# chaves.net
KiCad netlist of a schematic drawn in EAGLE
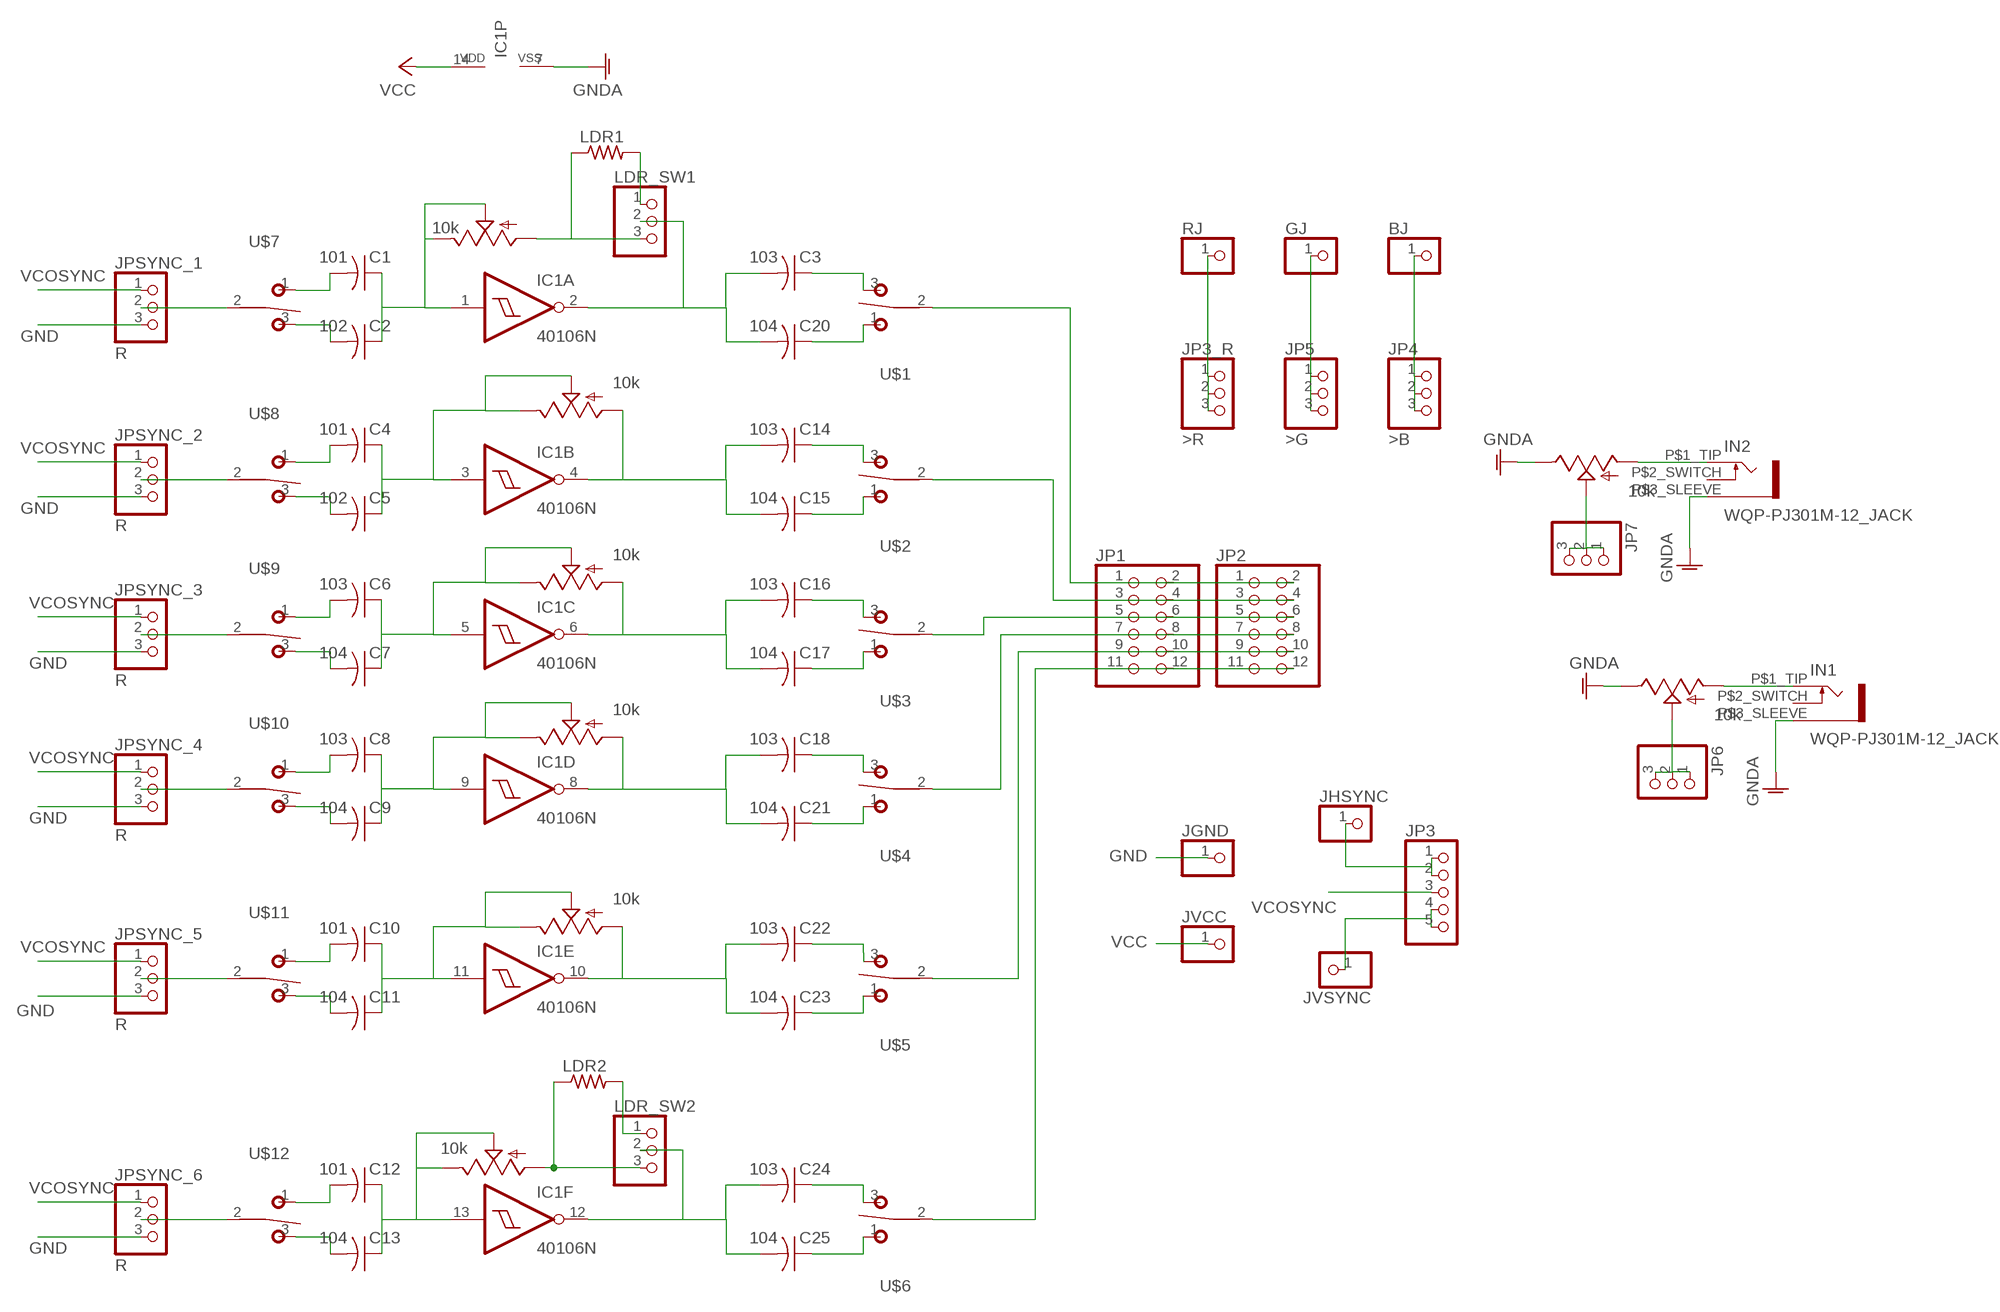
[diagram p0: schematic, sheet 1]

(export (version "E")
  (design (tool "Eeschema 10.0.6"))
  (components
    (comp (ref "BJ")
      (value "PINHD-1X1")
      (footprint "eagle-import:1X01")
      (libsource (lib "eagle-import") (part "PINHD-1X1"))
    )
    (comp (ref "C1")
      (value "101")
      (footprint "eagle-import:C050-025X075")
      (libsource (lib "eagle-import") (part "C-US050-025X075"))
    )
    (comp (ref "C2")
      (value "102")
      (footprint "eagle-import:C050-025X075")
      (libsource (lib "eagle-import") (part "C-US050-025X075"))
    )
    (comp (ref "C3")
      (value "103")
      (footprint "eagle-import:C050-025X075")
      (libsource (lib "eagle-import") (part "C-US050-025X075"))
    )
    (comp (ref "C4")
      (value "101")
      (footprint "eagle-import:C050-025X075")
      (libsource (lib "eagle-import") (part "C-US050-025X075"))
    )
    (comp (ref "C5")
      (value "102")
      (footprint "eagle-import:C050-025X075")
      (libsource (lib "eagle-import") (part "C-US050-025X075"))
    )
    (comp (ref "C6")
      (value "103")
      (footprint "eagle-import:C050-025X075")
      (libsource (lib "eagle-import") (part "C-US050-025X075"))
    )
    (comp (ref "C7")
      (value "104")
      (footprint "eagle-import:C050-025X075")
      (libsource (lib "eagle-import") (part "C-US050-025X075"))
    )
    (comp (ref "C8")
      (value "103")
      (footprint "eagle-import:C050-025X075")
      (libsource (lib "eagle-import") (part "C-US050-025X075"))
    )
    (comp (ref "C9")
      (value "104")
      (footprint "eagle-import:C050-025X075")
      (libsource (lib "eagle-import") (part "C-US050-025X075"))
    )
    (comp (ref "C10")
      (value "101")
      (footprint "eagle-import:C050-025X075")
      (libsource (lib "eagle-import") (part "C-US050-025X075"))
    )
    (comp (ref "C11")
      (value "104")
      (footprint "eagle-import:C050-025X075")
      (libsource (lib "eagle-import") (part "C-US050-025X075"))
    )
    (comp (ref "C12")
      (value "101")
      (footprint "eagle-import:C050-025X075")
      (libsource (lib "eagle-import") (part "C-US050-025X075"))
    )
    (comp (ref "C13")
      (value "104")
      (footprint "eagle-import:C050-025X075")
      (libsource (lib "eagle-import") (part "C-US050-025X075"))
    )
    (comp (ref "C14")
      (value "103")
      (footprint "eagle-import:C050-025X075")
      (libsource (lib "eagle-import") (part "C-US050-025X075"))
    )
    (comp (ref "C15")
      (value "104")
      (footprint "eagle-import:C050-025X075")
      (libsource (lib "eagle-import") (part "C-US050-025X075"))
    )
    (comp (ref "C16")
      (value "103")
      (footprint "eagle-import:C050-025X075")
      (libsource (lib "eagle-import") (part "C-US050-025X075"))
    )
    (comp (ref "C17")
      (value "104")
      (footprint "eagle-import:C050-025X075")
      (libsource (lib "eagle-import") (part "C-US050-025X075"))
    )
    (comp (ref "C18")
      (value "103")
      (footprint "eagle-import:C050-025X075")
      (libsource (lib "eagle-import") (part "C-US050-025X075"))
    )
    (comp (ref "C20")
      (value "104")
      (footprint "eagle-import:C050-025X075")
      (libsource (lib "eagle-import") (part "C-US050-025X075"))
    )
    (comp (ref "C21")
      (value "104")
      (footprint "eagle-import:C050-025X075")
      (libsource (lib "eagle-import") (part "C-US050-025X075"))
    )
    (comp (ref "C22")
      (value "103")
      (footprint "eagle-import:C050-025X075")
      (libsource (lib "eagle-import") (part "C-US050-025X075"))
    )
    (comp (ref "C23")
      (value "104")
      (footprint "eagle-import:C050-025X075")
      (libsource (lib "eagle-import") (part "C-US050-025X075"))
    )
    (comp (ref "C24")
      (value "103")
      (footprint "eagle-import:C050-025X075")
      (libsource (lib "eagle-import") (part "C-US050-025X075"))
    )
    (comp (ref "C25")
      (value "104")
      (footprint "eagle-import:C050-025X075")
      (libsource (lib "eagle-import") (part "C-US050-025X075"))
    )
    (comp (ref "GJ")
      (value "PINHD-1X1")
      (footprint "eagle-import:1X01")
      (libsource (lib "eagle-import") (part "PINHD-1X1"))
    )
    (comp (ref "IC1")
      (value "40106N")
      (footprint "eagle-import:DIL14")
      (libsource (lib "eagle-import") (part "40106N"))
    )
    (comp (ref "IN1")
      (value "WQP-PJ301M-12_JACK")
      (footprint "eagle-import:WQP-PJ301M-12_JACK")
      (libsource (lib "eagle-import") (part "WQP-PJ301M-12_JACK"))
    )
    (comp (ref "IN2")
      (value "WQP-PJ301M-12_JACK")
      (footprint "eagle-import:WQP-PJ301M-12_JACK")
      (libsource (lib "eagle-import") (part "WQP-PJ301M-12_JACK"))
    )
    (comp (ref "JGND")
      (value "PINHD-1X1")
      (footprint "eagle-import:1X01")
      (libsource (lib "eagle-import") (part "PINHD-1X1"))
    )
    (comp (ref "JHSYNC")
      (value "PINHD-1X1")
      (footprint "eagle-import:1X01")
      (libsource (lib "eagle-import") (part "PINHD-1X1"))
    )
    (comp (ref "JP1")
      (value "PINHD-2X6")
      (footprint "eagle-import:2X06")
      (libsource (lib "eagle-import") (part "PINHD-2X6"))
    )
    (comp (ref "JP2")
      (value "PINHD-2X6")
      (footprint "eagle-import:2X06")
      (libsource (lib "eagle-import") (part "PINHD-2X6"))
    )
    (comp (ref "JP3")
      (value "PINHD-1X5")
      (footprint "eagle-import:1X05")
      (libsource (lib "eagle-import") (part "PINHD-1X5"))
    )
    (comp (ref "JP3_R")
      (value ">R")
      (footprint "eagle-import:1X03")
      (libsource (lib "eagle-import") (part "pinhead_PINHD-1X3"))
    )
    (comp (ref "JP4")
      (value ">B")
      (footprint "eagle-import:1X03")
      (libsource (lib "eagle-import") (part "pinhead_PINHD-1X3"))
    )
    (comp (ref "JP5")
      (value ">G")
      (footprint "eagle-import:1X03")
      (libsource (lib "eagle-import") (part "pinhead_PINHD-1X3"))
    )
    (comp (ref "JP6")
      (value "PINHD-1X3CB")
      (footprint "eagle-import:1X03-CLEANBIG")
      (libsource (lib "eagle-import") (part "PINHD-1X3CB"))
    )
    (comp (ref "JP7")
      (value "PINHD-1X3CB")
      (footprint "eagle-import:1X03-CLEANBIG")
      (libsource (lib "eagle-import") (part "PINHD-1X3CB"))
    )
    (comp (ref "JPSYNC_1")
      (value "R")
      (footprint "eagle-import:1X03")
      (libsource (lib "eagle-import") (part "pinhead_PINHD-1X3"))
    )
    (comp (ref "JPSYNC_2")
      (value "R")
      (footprint "eagle-import:1X03")
      (libsource (lib "eagle-import") (part "pinhead_PINHD-1X3"))
    )
    (comp (ref "JPSYNC_3")
      (value "R")
      (footprint "eagle-import:1X03")
      (libsource (lib "eagle-import") (part "pinhead_PINHD-1X3"))
    )
    (comp (ref "JPSYNC_4")
      (value "R")
      (footprint "eagle-import:1X03")
      (libsource (lib "eagle-import") (part "pinhead_PINHD-1X3"))
    )
    (comp (ref "JPSYNC_5")
      (value "R")
      (footprint "eagle-import:1X03")
      (libsource (lib "eagle-import") (part "pinhead_PINHD-1X3"))
    )
    (comp (ref "JPSYNC_6")
      (value "R")
      (footprint "eagle-import:1X03")
      (libsource (lib "eagle-import") (part "pinhead_PINHD-1X3"))
    )
    (comp (ref "JVCC")
      (value "PINHD-1X1")
      (footprint "eagle-import:1X01")
      (libsource (lib "eagle-import") (part "PINHD-1X1"))
    )
    (comp (ref "JVSYNC")
      (value "PINHD-1X1")
      (footprint "eagle-import:1X01")
      (libsource (lib "eagle-import") (part "PINHD-1X1"))
    )
    (comp (ref "LDR1")
      (value "R-US_0204/7")
      (footprint "eagle-import:0204_7")
      (libsource (lib "eagle-import") (part "R-US_0204/7"))
    )
    (comp (ref "LDR2")
      (value "R-US_0204/7")
      (footprint "eagle-import:0204_7")
      (libsource (lib "eagle-import") (part "R-US_0204/7"))
    )
    (comp (ref "LDR_SW1")
      (value "PINHD-1X3")
      (footprint "eagle-import:1X03")
      (libsource (lib "eagle-import") (part "pinhead_PINHD-1X3"))
    )
    (comp (ref "LDR_SW2")
      (value "PINHD-1X3")
      (footprint "eagle-import:1X03")
      (libsource (lib "eagle-import") (part "pinhead_PINHD-1X3"))
    )
    (comp (ref "POT1")
      (value "10k")
      (footprint "eagle-import:ALPS_POT_VERTICAL")
      (libsource (lib "eagle-import") (part "POT_USVERTICAL"))
    )
    (comp (ref "POT2")
      (value "10k")
      (footprint "eagle-import:ALPS_POT_VERTICAL")
      (libsource (lib "eagle-import") (part "POT_USVERTICAL"))
    )
    (comp (ref "POT3")
      (value "10k")
      (footprint "eagle-import:ALPS_POT_VERTICAL")
      (libsource (lib "eagle-import") (part "POT_USVERTICAL"))
    )
    (comp (ref "POT4")
      (value "10k")
      (footprint "eagle-import:ALPS_POT_VERTICAL")
      (libsource (lib "eagle-import") (part "POT_USVERTICAL"))
    )
    (comp (ref "POT5")
      (value "10k")
      (footprint "eagle-import:ALPS_POT_VERTICAL")
      (libsource (lib "eagle-import") (part "POT_USVERTICAL"))
    )
    (comp (ref "POT6")
      (value "10k")
      (footprint "eagle-import:ALPS_POT_VERTICAL")
      (libsource (lib "eagle-import") (part "POT_USVERTICAL"))
    )
    (comp (ref "POT7")
      (value "10k")
      (footprint "eagle-import:ALPS_POT_VERTICAL")
      (libsource (lib "eagle-import") (part "POT_USVERTICAL"))
    )
    (comp (ref "POT8")
      (value "10k")
      (footprint "eagle-import:ALPS_POT_VERTICAL")
      (libsource (lib "eagle-import") (part "POT_USVERTICAL"))
    )
    (comp (ref "RJ")
      (value "PINHD-1X1")
      (footprint "eagle-import:1X01")
      (libsource (lib "eagle-import") (part "PINHD-1X1"))
    )
    (comp (ref "U$1")
      (value "T-80-T-SPDT-ON-OFF-ON")
      (footprint "eagle-import:M9040P")
      (libsource (lib "eagle-import") (part "T-80-T-SPDT-ON-OFF-ON"))
    )
    (comp (ref "U$2")
      (value "T-80-T-SPDT-ON-OFF-ON")
      (footprint "eagle-import:M9040P")
      (libsource (lib "eagle-import") (part "T-80-T-SPDT-ON-OFF-ON"))
    )
    (comp (ref "U$3")
      (value "T-80-T-SPDT-ON-OFF-ON")
      (footprint "eagle-import:M9040P")
      (libsource (lib "eagle-import") (part "T-80-T-SPDT-ON-OFF-ON"))
    )
    (comp (ref "U$4")
      (value "T-80-T-SPDT-ON-OFF-ON")
      (footprint "eagle-import:M9040P")
      (libsource (lib "eagle-import") (part "T-80-T-SPDT-ON-OFF-ON"))
    )
    (comp (ref "U$5")
      (value "T-80-T-SPDT-ON-OFF-ON")
      (footprint "eagle-import:M9040P")
      (libsource (lib "eagle-import") (part "T-80-T-SPDT-ON-OFF-ON"))
    )
    (comp (ref "U$6")
      (value "T-80-T-SPDT-ON-OFF-ON")
      (footprint "eagle-import:M9040P")
      (libsource (lib "eagle-import") (part "T-80-T-SPDT-ON-OFF-ON"))
    )
    (comp (ref "U$7")
      (value "T-80-T-SPDT-ON-OFF-ON")
      (footprint "eagle-import:M9040P")
      (libsource (lib "eagle-import") (part "T-80-T-SPDT-ON-OFF-ON"))
    )
    (comp (ref "U$8")
      (value "T-80-T-SPDT-ON-OFF-ON")
      (footprint "eagle-import:M9040P")
      (libsource (lib "eagle-import") (part "T-80-T-SPDT-ON-OFF-ON"))
    )
    (comp (ref "U$9")
      (value "T-80-T-SPDT-ON-OFF-ON")
      (footprint "eagle-import:M9040P")
      (libsource (lib "eagle-import") (part "T-80-T-SPDT-ON-OFF-ON"))
    )
    (comp (ref "U$10")
      (value "T-80-T-SPDT-ON-OFF-ON")
      (footprint "eagle-import:M9040P")
      (libsource (lib "eagle-import") (part "T-80-T-SPDT-ON-OFF-ON"))
    )
    (comp (ref "U$11")
      (value "T-80-T-SPDT-ON-OFF-ON")
      (footprint "eagle-import:M9040P")
      (libsource (lib "eagle-import") (part "T-80-T-SPDT-ON-OFF-ON"))
    )
    (comp (ref "U$12")
      (value "T-80-T-SPDT-ON-OFF-ON")
      (footprint "eagle-import:M9040P")
      (libsource (lib "eagle-import") (part "T-80-T-SPDT-ON-OFF-ON"))
    )
  )
  (nets
    (net (code "1") (name "/VCOSYNC") (class "Default")
      (node (ref "JP3") (pin "3") (pinfunction "3_3") (pintype "passive"))
      (node (ref "JPSYNC_1") (pin "1") (pinfunction "1_1") (pintype "passive"))
      (node (ref "JPSYNC_2") (pin "1") (pinfunction "1_1") (pintype "passive"))
      (node (ref "JPSYNC_3") (pin "1") (pinfunction "1_1") (pintype "passive"))
      (node (ref "JPSYNC_4") (pin "1") (pinfunction "1_1") (pintype "passive"))
      (node (ref "JPSYNC_5") (pin "1") (pinfunction "1_1") (pintype "passive"))
      (node (ref "JPSYNC_6") (pin "1") (pinfunction "1_1") (pintype "passive"))
    )
    (net (code "2") (name "GNDA") (class "Default")
      (node (ref "IC1") (pin "7") (pinfunction "VSS_7") (pintype "power_in"))
      (node (ref "IN1") (pin "P$3_SLEEVE") (pinfunction "1_P$3_SLEEVE") (pintype "passive"))
      (node (ref "IN2") (pin "P$3_SLEEVE") (pinfunction "1_P$3_SLEEVE") (pintype "passive"))
      (node (ref "JGND") (pin "1") (pinfunction "1_1") (pintype "passive"))
      (node (ref "JPSYNC_1") (pin "3") (pinfunction "3_3") (pintype "passive"))
      (node (ref "JPSYNC_2") (pin "3") (pinfunction "3_3") (pintype "passive"))
      (node (ref "JPSYNC_3") (pin "3") (pinfunction "3_3") (pintype "passive"))
      (node (ref "JPSYNC_4") (pin "3") (pinfunction "3_3") (pintype "passive"))
      (node (ref "JPSYNC_5") (pin "3") (pinfunction "3_3") (pintype "passive"))
      (node (ref "JPSYNC_6") (pin "3") (pinfunction "3_3") (pintype "passive"))
      (node (ref "POT7") (pin "P$1") (pinfunction "E_P$1") (pintype "passive"))
      (node (ref "POT8") (pin "P$1") (pinfunction "E_P$1") (pintype "passive"))
    )
    (net (code "3") (name "Net-(BJ-Pad1)") (class "Default")
      (node (ref "BJ") (pin "1") (pinfunction "1_1") (pintype "passive"))
      (node (ref "JP4") (pin "1") (pinfunction "1_1") (pintype "passive"))
      (node (ref "JP4") (pin "2") (pinfunction "2_2") (pintype "passive"))
      (node (ref "JP4") (pin "3") (pinfunction "3_3") (pintype "passive"))
    )
    (net (code "4") (name "Net-(GJ-Pad1)") (class "Default")
      (node (ref "GJ") (pin "1") (pinfunction "1_1") (pintype "passive"))
      (node (ref "JP5") (pin "1") (pinfunction "1_1") (pintype "passive"))
      (node (ref "JP5") (pin "2") (pinfunction "2_2") (pintype "passive"))
      (node (ref "JP5") (pin "3") (pinfunction "3_3") (pintype "passive"))
    )
    (net (code "5") (name "Net-(IC1A-I)") (class "Default")
      (node (ref "C1") (pin "1") (pinfunction "1_1") (pintype "passive"))
      (node (ref "C2") (pin "1") (pinfunction "1_1") (pintype "passive"))
      (node (ref "IC1") (pin "1") (pinfunction "I_1") (pintype "input"))
      (node (ref "POT1") (pin "P$1") (pinfunction "E_P$1") (pintype "passive"))
      (node (ref "POT1") (pin "P$2") (pinfunction "S_P$2") (pintype "passive"))
    )
    (net (code "6") (name "Net-(IC1A-O)") (class "Default")
      (node (ref "C20") (pin "2") (pinfunction "2_2") (pintype "passive"))
      (node (ref "C3") (pin "2") (pinfunction "2_2") (pintype "passive"))
      (node (ref "IC1") (pin "2") (pinfunction "O_2") (pintype "output"))
      (node (ref "LDR_SW1") (pin "2") (pinfunction "2_2") (pintype "passive"))
    )
    (net (code "7") (name "Net-(IC1B-I)") (class "Default")
      (node (ref "C4") (pin "1") (pinfunction "1_1") (pintype "passive"))
      (node (ref "C5") (pin "1") (pinfunction "1_1") (pintype "passive"))
      (node (ref "IC1") (pin "3") (pinfunction "I_3") (pintype "input"))
      (node (ref "POT2") (pin "P$1") (pinfunction "E_P$1") (pintype "passive"))
      (node (ref "POT2") (pin "P$2") (pinfunction "S_P$2") (pintype "passive"))
    )
    (net (code "8") (name "Net-(IC1B-O)") (class "Default")
      (node (ref "C14") (pin "2") (pinfunction "2_2") (pintype "passive"))
      (node (ref "C15") (pin "2") (pinfunction "2_2") (pintype "passive"))
      (node (ref "IC1") (pin "4") (pinfunction "O_4") (pintype "output"))
      (node (ref "POT2") (pin "P$3") (pinfunction "A_P$3") (pintype "passive"))
    )
    (net (code "9") (name "Net-(IC1C-I)") (class "Default")
      (node (ref "C6") (pin "1") (pinfunction "1_1") (pintype "passive"))
      (node (ref "C7") (pin "1") (pinfunction "1_1") (pintype "passive"))
      (node (ref "IC1") (pin "5") (pinfunction "I_5") (pintype "input"))
      (node (ref "POT3") (pin "P$1") (pinfunction "E_P$1") (pintype "passive"))
      (node (ref "POT3") (pin "P$2") (pinfunction "S_P$2") (pintype "passive"))
    )
    (net (code "10") (name "Net-(IC1C-O)") (class "Default")
      (node (ref "C16") (pin "2") (pinfunction "2_2") (pintype "passive"))
      (node (ref "C17") (pin "2") (pinfunction "2_2") (pintype "passive"))
      (node (ref "IC1") (pin "6") (pinfunction "O_6") (pintype "output"))
      (node (ref "POT3") (pin "P$3") (pinfunction "A_P$3") (pintype "passive"))
    )
    (net (code "11") (name "Net-(IC1D-I)") (class "Default")
      (node (ref "C8") (pin "1") (pinfunction "1_1") (pintype "passive"))
      (node (ref "C9") (pin "1") (pinfunction "1_1") (pintype "passive"))
      (node (ref "IC1") (pin "9") (pinfunction "I_9") (pintype "input"))
      (node (ref "POT4") (pin "P$1") (pinfunction "E_P$1") (pintype "passive"))
      (node (ref "POT4") (pin "P$2") (pinfunction "S_P$2") (pintype "passive"))
    )
    (net (code "12") (name "Net-(IC1D-O)") (class "Default")
      (node (ref "C18") (pin "2") (pinfunction "2_2") (pintype "passive"))
      (node (ref "C21") (pin "2") (pinfunction "2_2") (pintype "passive"))
      (node (ref "IC1") (pin "8") (pinfunction "O_8") (pintype "output"))
      (node (ref "POT4") (pin "P$3") (pinfunction "A_P$3") (pintype "passive"))
    )
    (net (code "13") (name "Net-(IC1E-I)") (class "Default")
      (node (ref "C10") (pin "1") (pinfunction "1_1") (pintype "passive"))
      (node (ref "C11") (pin "1") (pinfunction "1_1") (pintype "passive"))
      (node (ref "IC1") (pin "11") (pinfunction "I_11") (pintype "input"))
      (node (ref "POT5") (pin "P$1") (pinfunction "E_P$1") (pintype "passive"))
      (node (ref "POT5") (pin "P$2") (pinfunction "S_P$2") (pintype "passive"))
    )
    (net (code "14") (name "Net-(IC1E-O)") (class "Default")
      (node (ref "C22") (pin "2") (pinfunction "2_2") (pintype "passive"))
      (node (ref "C23") (pin "2") (pinfunction "2_2") (pintype "passive"))
      (node (ref "IC1") (pin "10") (pinfunction "O_10") (pintype "output"))
      (node (ref "POT5") (pin "P$3") (pinfunction "A_P$3") (pintype "passive"))
    )
    (net (code "15") (name "Net-(IC1F-I)") (class "Default")
      (node (ref "C12") (pin "1") (pinfunction "1_1") (pintype "passive"))
      (node (ref "C13") (pin "1") (pinfunction "1_1") (pintype "passive"))
      (node (ref "IC1") (pin "13") (pinfunction "I_13") (pintype "input"))
      (node (ref "POT6") (pin "P$1") (pinfunction "E_P$1") (pintype "passive"))
      (node (ref "POT6") (pin "P$2") (pinfunction "S_P$2") (pintype "passive"))
    )
    (net (code "16") (name "Net-(IC1F-O)") (class "Default")
      (node (ref "C24") (pin "2") (pinfunction "2_2") (pintype "passive"))
      (node (ref "C25") (pin "2") (pinfunction "2_2") (pintype "passive"))
      (node (ref "IC1") (pin "12") (pinfunction "O_12") (pintype "output"))
      (node (ref "LDR_SW2") (pin "2") (pinfunction "2_2") (pintype "passive"))
    )
    (net (code "17") (name "Net-(IN1-2)") (class "Default")
      (node (ref "IN1") (pin "P$1_TIP") (pinfunction "2_P$1_TIP") (pintype "passive"))
      (node (ref "POT7") (pin "P$3") (pinfunction "A_P$3") (pintype "passive"))
    )
    (net (code "18") (name "Net-(IN2-2)") (class "Default")
      (node (ref "IN2") (pin "P$1_TIP") (pinfunction "2_P$1_TIP") (pintype "passive"))
      (node (ref "POT8") (pin "P$3") (pinfunction "A_P$3") (pintype "passive"))
    )
    (net (code "19") (name "Net-(JHSYNC-Pad1)") (class "Default")
      (node (ref "JHSYNC") (pin "1") (pinfunction "1_1") (pintype "passive"))
      (node (ref "JP3") (pin "1") (pinfunction "1_1") (pintype "passive"))
      (node (ref "JP3") (pin "2") (pinfunction "2_2") (pintype "passive"))
    )
    (net (code "20") (name "Net-(JP3-Pad4)") (class "Default")
      (node (ref "JP3") (pin "4") (pinfunction "4_4") (pintype "passive"))
      (node (ref "JP3") (pin "5") (pinfunction "5_5") (pintype "passive"))
      (node (ref "JVSYNC") (pin "1") (pinfunction "1_1") (pintype "passive"))
    )
    (net (code "21") (name "Net-(JP3_R-Pad1)") (class "Default")
      (node (ref "JP3_R") (pin "1") (pinfunction "1_1") (pintype "passive"))
      (node (ref "JP3_R") (pin "2") (pinfunction "2_2") (pintype "passive"))
      (node (ref "JP3_R") (pin "3") (pinfunction "3_3") (pintype "passive"))
      (node (ref "RJ") (pin "1") (pinfunction "1_1") (pintype "passive"))
    )
    (net (code "22") (name "Net-(LDR1-Pad2)") (class "Default")
      (node (ref "LDR1") (pin "2") (pinfunction "2_2") (pintype "passive"))
      (node (ref "LDR_SW1") (pin "1") (pinfunction "1_1") (pintype "passive"))
    )
    (net (code "23") (name "Net-(LDR2-Pad2)") (class "Default")
      (node (ref "LDR2") (pin "2") (pinfunction "2_2") (pintype "passive"))
      (node (ref "LDR_SW2") (pin "1") (pinfunction "1_1") (pintype "passive"))
    )
    (net (code "24") (name "Net-(POT1-A)") (class "Default")
      (node (ref "LDR1") (pin "1") (pinfunction "1_1") (pintype "passive"))
      (node (ref "LDR_SW1") (pin "3") (pinfunction "3_3") (pintype "passive"))
      (node (ref "POT1") (pin "P$3") (pinfunction "A_P$3") (pintype "passive"))
    )
    (net (code "25") (name "Net-(POT6-A)") (class "Default")
      (node (ref "LDR2") (pin "1") (pinfunction "1_1") (pintype "passive"))
      (node (ref "LDR_SW2") (pin "3") (pinfunction "3_3") (pintype "passive"))
      (node (ref "POT6") (pin "P$3") (pinfunction "A_P$3") (pintype "passive"))
    )
    (net (code "26") (name "Net-(POT7-S)") (class "Default")
      (node (ref "JP6") (pin "1") (pinfunction "1_1") (pintype "passive"))
      (node (ref "JP6") (pin "2") (pinfunction "2_2") (pintype "passive"))
      (node (ref "JP6") (pin "3") (pinfunction "3_3") (pintype "passive"))
      (node (ref "POT7") (pin "P$2") (pinfunction "S_P$2") (pintype "passive"))
    )
    (net (code "27") (name "Net-(POT8-S)") (class "Default")
      (node (ref "JP7") (pin "1") (pinfunction "1_1") (pintype "passive"))
      (node (ref "JP7") (pin "2") (pinfunction "2_2") (pintype "passive"))
      (node (ref "JP7") (pin "3") (pinfunction "3_3") (pintype "passive"))
      (node (ref "POT8") (pin "P$2") (pinfunction "S_P$2") (pintype "passive"))
    )
    (net (code "28") (name "Net-(U$1-O)") (class "Default")
      (node (ref "C20") (pin "1") (pinfunction "1_1") (pintype "passive"))
      (node (ref "U$1") (pin "1") (pinfunction "O_1") (pintype "passive"))
    )
    (net (code "29") (name "Net-(U$1-P)") (class "Default")
      (node (ref "JP1") (pin "1") (pinfunction "1_1") (pintype "passive"))
      (node (ref "JP1") (pin "2") (pinfunction "2_2") (pintype "passive"))
      (node (ref "JP2") (pin "1") (pinfunction "1_1") (pintype "passive"))
      (node (ref "JP2") (pin "2") (pinfunction "2_2") (pintype "passive"))
      (node (ref "U$1") (pin "2") (pinfunction "P_2") (pintype "passive"))
    )
    (net (code "30") (name "Net-(U$1-S)") (class "Default")
      (node (ref "C3") (pin "1") (pinfunction "1_1") (pintype "passive"))
      (node (ref "U$1") (pin "3") (pinfunction "S_3") (pintype "passive"))
    )
    (net (code "31") (name "Net-(U$2-O)") (class "Default")
      (node (ref "C15") (pin "1") (pinfunction "1_1") (pintype "passive"))
      (node (ref "U$2") (pin "1") (pinfunction "O_1") (pintype "passive"))
    )
    (net (code "32") (name "Net-(U$2-P)") (class "Default")
      (node (ref "JP1") (pin "3") (pinfunction "3_3") (pintype "passive"))
      (node (ref "JP1") (pin "4") (pinfunction "4_4") (pintype "passive"))
      (node (ref "JP2") (pin "3") (pinfunction "3_3") (pintype "passive"))
      (node (ref "JP2") (pin "4") (pinfunction "4_4") (pintype "passive"))
      (node (ref "U$2") (pin "2") (pinfunction "P_2") (pintype "passive"))
    )
    (net (code "33") (name "Net-(U$2-S)") (class "Default")
      (node (ref "C14") (pin "1") (pinfunction "1_1") (pintype "passive"))
      (node (ref "U$2") (pin "3") (pinfunction "S_3") (pintype "passive"))
    )
    (net (code "34") (name "Net-(U$3-O)") (class "Default")
      (node (ref "C17") (pin "1") (pinfunction "1_1") (pintype "passive"))
      (node (ref "U$3") (pin "1") (pinfunction "O_1") (pintype "passive"))
    )
    (net (code "35") (name "Net-(U$3-P)") (class "Default")
      (node (ref "JP1") (pin "5") (pinfunction "5_5") (pintype "passive"))
      (node (ref "JP1") (pin "6") (pinfunction "6_6") (pintype "passive"))
      (node (ref "JP2") (pin "5") (pinfunction "5_5") (pintype "passive"))
      (node (ref "JP2") (pin "6") (pinfunction "6_6") (pintype "passive"))
      (node (ref "U$3") (pin "2") (pinfunction "P_2") (pintype "passive"))
    )
    (net (code "36") (name "Net-(U$3-S)") (class "Default")
      (node (ref "C16") (pin "1") (pinfunction "1_1") (pintype "passive"))
      (node (ref "U$3") (pin "3") (pinfunction "S_3") (pintype "passive"))
    )
    (net (code "37") (name "Net-(U$4-O)") (class "Default")
      (node (ref "C21") (pin "1") (pinfunction "1_1") (pintype "passive"))
      (node (ref "U$4") (pin "1") (pinfunction "O_1") (pintype "passive"))
    )
    (net (code "38") (name "Net-(U$4-P)") (class "Default")
      (node (ref "JP1") (pin "7") (pinfunction "7_7") (pintype "passive"))
      (node (ref "JP1") (pin "8") (pinfunction "8_8") (pintype "passive"))
      (node (ref "JP2") (pin "7") (pinfunction "7_7") (pintype "passive"))
      (node (ref "JP2") (pin "8") (pinfunction "8_8") (pintype "passive"))
      (node (ref "U$4") (pin "2") (pinfunction "P_2") (pintype "passive"))
    )
    (net (code "39") (name "Net-(U$4-S)") (class "Default")
      (node (ref "C18") (pin "1") (pinfunction "1_1") (pintype "passive"))
      (node (ref "U$4") (pin "3") (pinfunction "S_3") (pintype "passive"))
    )
    (net (code "40") (name "Net-(U$5-O)") (class "Default")
      (node (ref "C23") (pin "1") (pinfunction "1_1") (pintype "passive"))
      (node (ref "U$5") (pin "1") (pinfunction "O_1") (pintype "passive"))
    )
    (net (code "41") (name "Net-(U$5-P)") (class "Default")
      (node (ref "JP1") (pin "10") (pinfunction "10_10") (pintype "passive"))
      (node (ref "JP1") (pin "9") (pinfunction "9_9") (pintype "passive"))
      (node (ref "JP2") (pin "10") (pinfunction "10_10") (pintype "passive"))
      (node (ref "JP2") (pin "9") (pinfunction "9_9") (pintype "passive"))
      (node (ref "U$5") (pin "2") (pinfunction "P_2") (pintype "passive"))
    )
    (net (code "42") (name "Net-(U$5-S)") (class "Default")
      (node (ref "C22") (pin "1") (pinfunction "1_1") (pintype "passive"))
      (node (ref "U$5") (pin "3") (pinfunction "S_3") (pintype "passive"))
    )
    (net (code "43") (name "Net-(U$6-O)") (class "Default")
      (node (ref "C25") (pin "1") (pinfunction "1_1") (pintype "passive"))
      (node (ref "U$6") (pin "1") (pinfunction "O_1") (pintype "passive"))
    )
    (net (code "44") (name "Net-(U$6-P)") (class "Default")
      (node (ref "JP1") (pin "11") (pinfunction "11_11") (pintype "passive"))
      (node (ref "JP1") (pin "12") (pinfunction "12_12") (pintype "passive"))
      (node (ref "JP2") (pin "11") (pinfunction "11_11") (pintype "passive"))
      (node (ref "JP2") (pin "12") (pinfunction "12_12") (pintype "passive"))
      (node (ref "U$6") (pin "2") (pinfunction "P_2") (pintype "passive"))
    )
    (net (code "45") (name "Net-(U$6-S)") (class "Default")
      (node (ref "C24") (pin "1") (pinfunction "1_1") (pintype "passive"))
      (node (ref "U$6") (pin "3") (pinfunction "S_3") (pintype "passive"))
    )
    (net (code "46") (name "Net-(U$7-O)") (class "Default")
      (node (ref "C1") (pin "2") (pinfunction "2_2") (pintype "passive"))
      (node (ref "U$7") (pin "1") (pinfunction "O_1") (pintype "passive"))
    )
    (net (code "47") (name "Net-(U$7-P)") (class "Default")
      (node (ref "JPSYNC_1") (pin "2") (pinfunction "2_2") (pintype "passive"))
      (node (ref "U$7") (pin "2") (pinfunction "P_2") (pintype "passive"))
    )
    (net (code "48") (name "Net-(U$7-S)") (class "Default")
      (node (ref "C2") (pin "2") (pinfunction "2_2") (pintype "passive"))
      (node (ref "U$7") (pin "3") (pinfunction "S_3") (pintype "passive"))
    )
    (net (code "49") (name "Net-(U$8-O)") (class "Default")
      (node (ref "C4") (pin "2") (pinfunction "2_2") (pintype "passive"))
      (node (ref "U$8") (pin "1") (pinfunction "O_1") (pintype "passive"))
    )
    (net (code "50") (name "Net-(U$8-P)") (class "Default")
      (node (ref "JPSYNC_2") (pin "2") (pinfunction "2_2") (pintype "passive"))
      (node (ref "U$8") (pin "2") (pinfunction "P_2") (pintype "passive"))
    )
    (net (code "51") (name "Net-(U$8-S)") (class "Default")
      (node (ref "C5") (pin "2") (pinfunction "2_2") (pintype "passive"))
      (node (ref "U$8") (pin "3") (pinfunction "S_3") (pintype "passive"))
    )
    (net (code "52") (name "Net-(U$9-O)") (class "Default")
      (node (ref "C6") (pin "2") (pinfunction "2_2") (pintype "passive"))
      (node (ref "U$9") (pin "1") (pinfunction "O_1") (pintype "passive"))
    )
    (net (code "53") (name "Net-(U$9-P)") (class "Default")
      (node (ref "JPSYNC_3") (pin "2") (pinfunction "2_2") (pintype "passive"))
      (node (ref "U$9") (pin "2") (pinfunction "P_2") (pintype "passive"))
    )
    (net (code "54") (name "Net-(U$9-S)") (class "Default")
      (node (ref "C7") (pin "2") (pinfunction "2_2") (pintype "passive"))
      (node (ref "U$9") (pin "3") (pinfunction "S_3") (pintype "passive"))
    )
    (net (code "55") (name "Net-(U$10-O)") (class "Default")
      (node (ref "C8") (pin "2") (pinfunction "2_2") (pintype "passive"))
      (node (ref "U$10") (pin "1") (pinfunction "O_1") (pintype "passive"))
    )
    (net (code "56") (name "Net-(U$10-P)") (class "Default")
      (node (ref "JPSYNC_4") (pin "2") (pinfunction "2_2") (pintype "passive"))
      (node (ref "U$10") (pin "2") (pinfunction "P_2") (pintype "passive"))
    )
    (net (code "57") (name "Net-(U$10-S)") (class "Default")
      (node (ref "C9") (pin "2") (pinfunction "2_2") (pintype "passive"))
      (node (ref "U$10") (pin "3") (pinfunction "S_3") (pintype "passive"))
    )
    (net (code "58") (name "Net-(U$11-O)") (class "Default")
      (node (ref "C10") (pin "2") (pinfunction "2_2") (pintype "passive"))
      (node (ref "U$11") (pin "1") (pinfunction "O_1") (pintype "passive"))
    )
    (net (code "59") (name "Net-(U$11-P)") (class "Default")
      (node (ref "JPSYNC_5") (pin "2") (pinfunction "2_2") (pintype "passive"))
      (node (ref "U$11") (pin "2") (pinfunction "P_2") (pintype "passive"))
    )
    (net (code "60") (name "Net-(U$11-S)") (class "Default")
      (node (ref "C11") (pin "2") (pinfunction "2_2") (pintype "passive"))
      (node (ref "U$11") (pin "3") (pinfunction "S_3") (pintype "passive"))
    )
    (net (code "61") (name "Net-(U$12-O)") (class "Default")
      (node (ref "C12") (pin "2") (pinfunction "2_2") (pintype "passive"))
      (node (ref "U$12") (pin "1") (pinfunction "O_1") (pintype "passive"))
    )
    (net (code "62") (name "Net-(U$12-P)") (class "Default")
      (node (ref "JPSYNC_6") (pin "2") (pinfunction "2_2") (pintype "passive"))
      (node (ref "U$12") (pin "2") (pinfunction "P_2") (pintype "passive"))
    )
    (net (code "63") (name "Net-(U$12-S)") (class "Default")
      (node (ref "C13") (pin "2") (pinfunction "2_2") (pintype "passive"))
      (node (ref "U$12") (pin "3") (pinfunction "S_3") (pintype "passive"))
    )
    (net (code "64") (name "VCC") (class "Default")
      (node (ref "IC1") (pin "14") (pinfunction "VDD_14") (pintype "power_in"))
      (node (ref "JVCC") (pin "1") (pinfunction "1_1") (pintype "passive"))
    )
    (net (code "65") (name "unconnected-(IN1-3-PadP$2_SWITCH)") (class "Default")
      (node (ref "IN1") (pin "P$2_SWITCH") (pinfunction "3_P$2_SWITCH") (pintype "passive"))
    )
    (net (code "66") (name "unconnected-(IN2-3-PadP$2_SWITCH)") (class "Default")
      (node (ref "IN2") (pin "P$2_SWITCH") (pinfunction "3_P$2_SWITCH") (pintype "passive"))
    )
  )
)
